# x-IMU3-SA-A2.net
KiCad netlist of a schematic drawn in Altium Designer
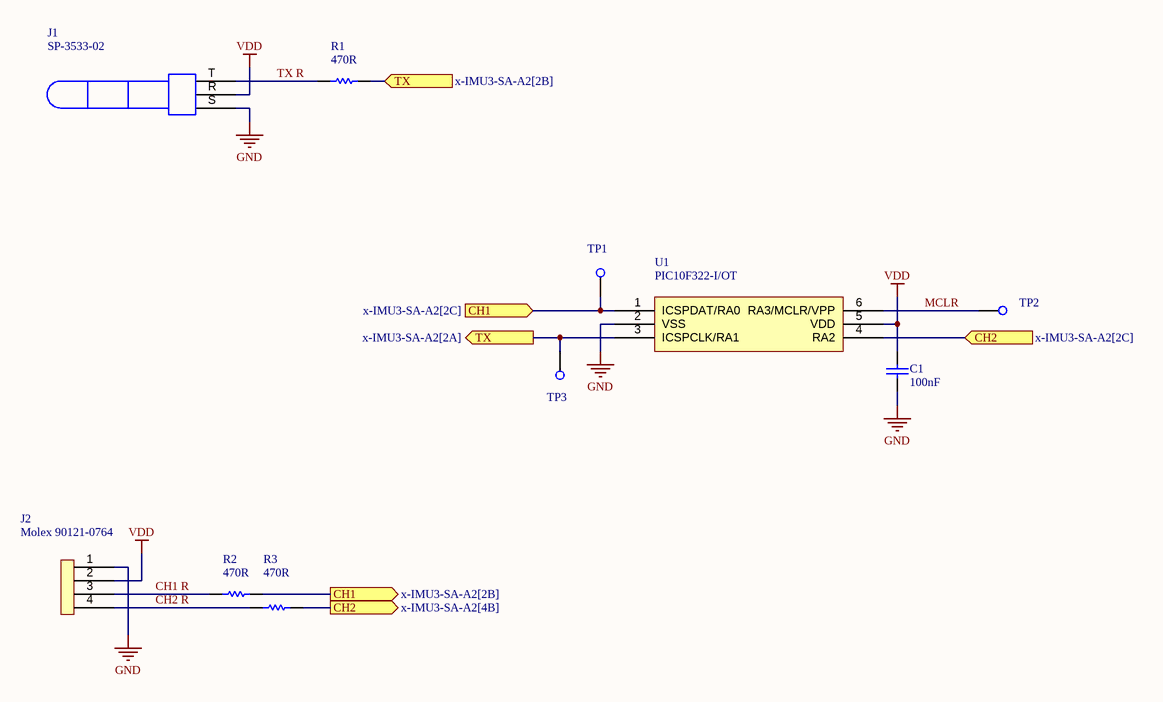
[diagram p0: x-IMU3-SA-A2.SchDoc]

(export (version "E")
  (design (tool "Eeschema 10.0.6"))
  (components
    (comp (ref "C1") (value "100nF") (footprint "Capacitor 0402") (libsource (lib "x-io") (part "Capacitor")))
    (comp (ref "J1")
      (value "SP-3533-02")
      (footprint "SP-3533-02")
      (libsource (lib "x-io") (part "SP-3533-02"))
    )
    (comp (ref "J2")
      (value "Molex 90121-0764")
      (footprint "Molex 90121-0764")
      (libsource (lib "x-io") (part "Molex 90121-0764"))
    )
    (comp (ref "R1") (value "470R") (footprint "Resistor 0402") (libsource (lib "x-io") (part "Resistor")))
    (comp (ref "R2") (value "470R") (footprint "Resistor 0402") (libsource (lib "x-io") (part "Resistor")))
    (comp (ref "R3") (value "470R") (footprint "Resistor 0402") (libsource (lib "x-io") (part "Resistor")))
    (comp (ref "TP1")
      (value "Test Point")
      (footprint "Test Point 1mm")
      (libsource (lib "x-io") (part "Test Point"))
    )
    (comp (ref "TP2")
      (value "Test Point")
      (footprint "Test Point 1mm")
      (libsource (lib "x-io") (part "Test Point"))
    )
    (comp (ref "TP3")
      (value "Test Point")
      (footprint "Test Point 1mm")
      (libsource (lib "x-io") (part "Test Point"))
    )
    (comp (ref "U1")
      (value "PIC10F322-I/OT")
      (footprint "SOT-23-6")
      (libsource (lib "x-io") (part "PIC10F322-I/OT"))
    )
  )
  (nets
    (net (code "1") (name "/CH1") (class "Default")
      (node (ref "R2") (pin "2") (pinfunction "2_2") (pintype "passive"))
      (node (ref "TP1") (pin "1") (pinfunction "1_1") (pintype "passive"))
      (node (ref "U1") (pin "1") (pinfunction "ICSPDAT/RA0_1") (pintype "passive"))
    )
    (net (code "2") (name "/CH1 R") (class "Default")
      (node (ref "J2") (pin "3") (pinfunction "3_3") (pintype "passive"))
      (node (ref "R2") (pin "1") (pinfunction "1_1") (pintype "passive"))
    )
    (net (code "3") (name "/CH2") (class "Default")
      (node (ref "R3") (pin "2") (pinfunction "2_2") (pintype "passive"))
      (node (ref "U1") (pin "4") (pinfunction "RA2_4") (pintype "passive"))
    )
    (net (code "4") (name "/CH2 R") (class "Default")
      (node (ref "J2") (pin "4") (pinfunction "4_4") (pintype "passive"))
      (node (ref "R3") (pin "1") (pinfunction "1_1") (pintype "passive"))
    )
    (net (code "5") (name "/MCLR") (class "Default")
      (node (ref "TP2") (pin "1") (pinfunction "1_1") (pintype "passive"))
      (node (ref "U1") (pin "6") (pinfunction "RA3/MCLR/VPP_6") (pintype "passive"))
    )
    (net (code "6") (name "/TX") (class "Default")
      (node (ref "R1") (pin "2") (pinfunction "2_2") (pintype "passive"))
      (node (ref "TP3") (pin "1") (pinfunction "1_1") (pintype "passive"))
      (node (ref "U1") (pin "3") (pinfunction "ICSPCLK/RA1_3") (pintype "passive"))
    )
    (net (code "7") (name "/TX R") (class "Default")
      (node (ref "J1") (pin "T") (pinfunction "T_T") (pintype "passive"))
      (node (ref "R1") (pin "1") (pinfunction "1_1") (pintype "passive"))
    )
    (net (code "8") (name "GND") (class "Default")
      (node (ref "C1") (pin "1") (pinfunction "1_1") (pintype "passive"))
      (node (ref "J1") (pin "S") (pinfunction "S_S") (pintype "passive"))
      (node (ref "J2") (pin "1") (pinfunction "1_1") (pintype "passive"))
      (node (ref "U1") (pin "2") (pinfunction "VSS_2") (pintype "passive"))
    )
    (net (code "9") (name "VDD") (class "Default")
      (node (ref "C1") (pin "2") (pinfunction "2_2") (pintype "passive"))
      (node (ref "J1") (pin "R") (pinfunction "R_R") (pintype "passive"))
      (node (ref "J2") (pin "2") (pinfunction "2_2") (pintype "passive"))
      (node (ref "U1") (pin "5") (pinfunction "VDD_5") (pintype "passive"))
    )
  )
)
